# ARDUINO_POWER_UNIT1.net
KiCad netlist of a schematic drawn in EAGLE
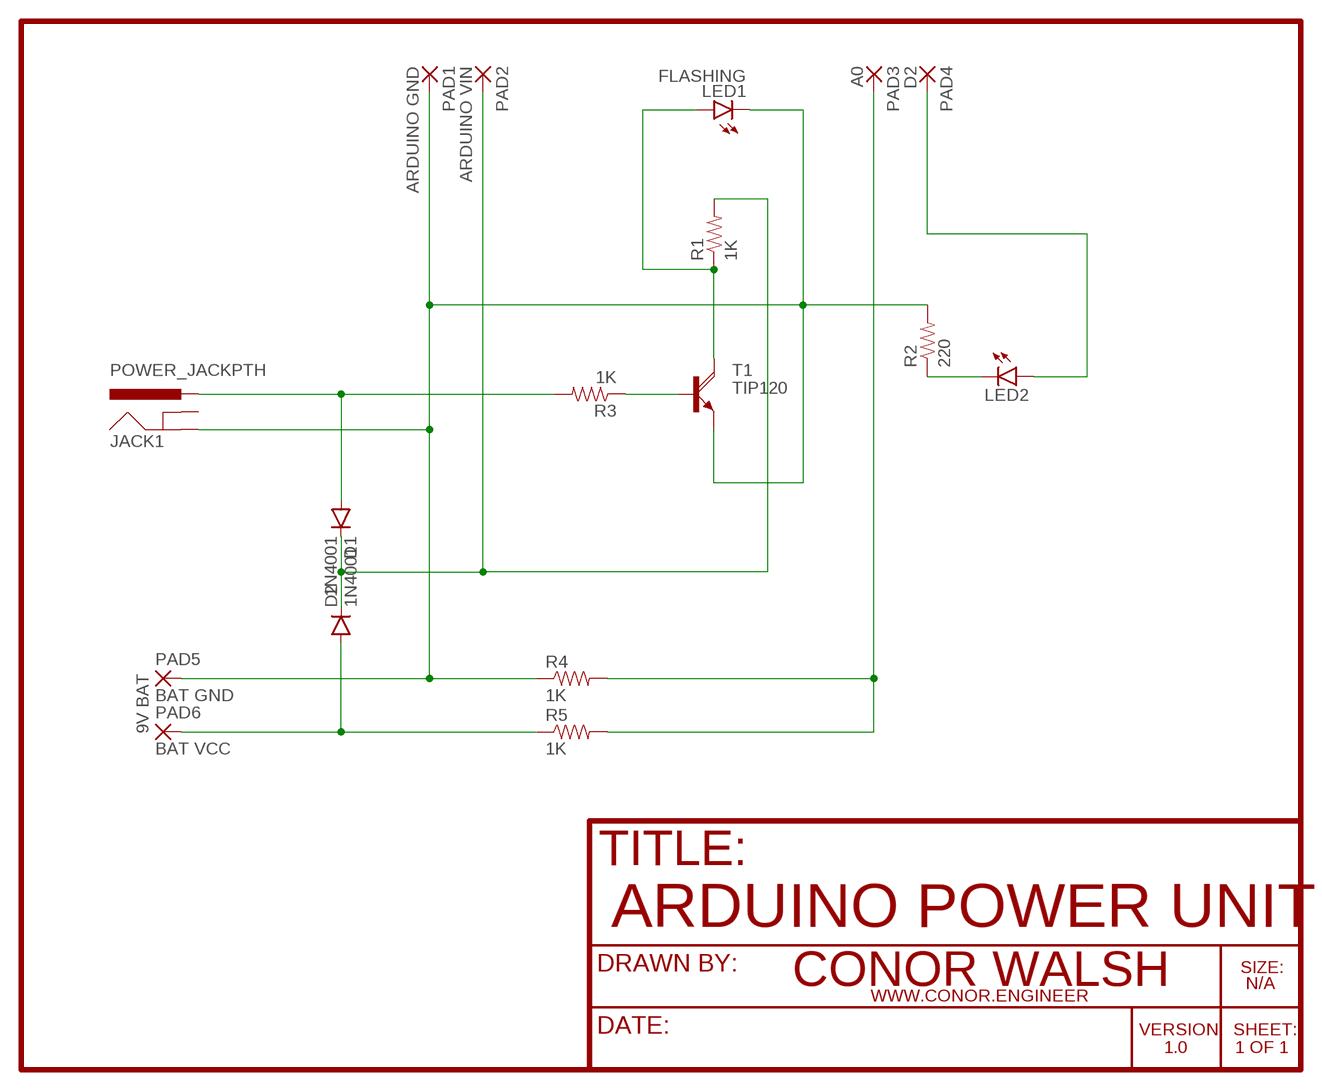
[diagram p0: schematic, sheet 1]

(export (version "E")
  (design (tool "Eeschema 10.0.6"))
  (components
    (comp (ref "D1")
      (value "1N4001")
      (footprint "eagle-import:DIODE-1N4148")
      (libsource (lib "eagle-import") (part "DIODE1N4148"))
    )
    (comp (ref "D2")
      (value "1N4001")
      (footprint "eagle-import:DIODE-1N4148")
      (libsource (lib "eagle-import") (part "DIODE1N4148"))
    )
    (comp (ref "JACK1")
      (value "POWER_JACKPTH")
      (footprint "eagle-import:POWER_JACK_PTH")
      (libsource (lib "eagle-import") (part "POWER_JACKPTH"))
    )
    (comp (ref "LED1")
      (value "FLASHING")
      (footprint "eagle-import:LED5MM")
      (libsource (lib "eagle-import") (part "LED5MM"))
    )
    (comp (ref "LED2")
      (value "LED5MM")
      (footprint "eagle-import:LED5MM")
      (libsource (lib "eagle-import") (part "LED5MM"))
    )
    (comp (ref "PAD1")
      (value "ARDUINO GND")
      (footprint "eagle-import:2,54_0,9")
      (libsource (lib "eagle-import") (part "2,54/0,9"))
    )
    (comp (ref "PAD2")
      (value "ARDUINO VIN")
      (footprint "eagle-import:2,54_0,9")
      (libsource (lib "eagle-import") (part "2,54/0,9"))
    )
    (comp (ref "PAD3")
      (value "A0")
      (footprint "eagle-import:2,54_0,9")
      (libsource (lib "eagle-import") (part "2,54/0,9"))
    )
    (comp (ref "PAD4")
      (value "D2")
      (footprint "eagle-import:2,54_0,9")
      (libsource (lib "eagle-import") (part "2,54/0,9"))
    )
    (comp (ref "PAD5")
      (value "BAT GND")
      (footprint "eagle-import:2,54_0,9")
      (libsource (lib "eagle-import") (part "2,54/0,9"))
    )
    (comp (ref "PAD6")
      (value "BAT VCC")
      (footprint "eagle-import:2,54_0,9")
      (libsource (lib "eagle-import") (part "2,54/0,9"))
    )
    (comp (ref "R1")
      (value "1K")
      (footprint "eagle-import:AXIAL-0.4")
      (libsource (lib "eagle-import") (part "RESISTORPTH-1/4W"))
    )
    (comp (ref "R2")
      (value "220")
      (footprint "eagle-import:AXIAL-0.4")
      (libsource (lib "eagle-import") (part "RESISTORPTH-1/4W"))
    )
    (comp (ref "R3")
      (value "1K")
      (footprint "eagle-import:AXIAL-0.4")
      (libsource (lib "eagle-import") (part "RESISTORPTH-1/4W"))
    )
    (comp (ref "R4")
      (value "1K")
      (footprint "eagle-import:AXIAL-0.4")
      (libsource (lib "eagle-import") (part "RESISTORPTH-1/4W"))
    )
    (comp (ref "R5")
      (value "1K")
      (footprint "eagle-import:AXIAL-0.4")
      (libsource (lib "eagle-import") (part "RESISTORPTH-1/4W"))
    )
    (comp (ref "T1")
      (value "TIP120")
      (footprint "eagle-import:TO220AH")
      (libsource (lib "eagle-import") (part "TIP120"))
    )
  )
  (nets
    (net (code "1") (name "Net-(LED1-C)") (class "Default")
      (node (ref "JACK1") (pin "GND") (pinfunction "GND_GND") (pintype "bidirectional"))
      (node (ref "LED1") (pin "K") (pinfunction "C_K") (pintype "passive"))
      (node (ref "PAD1") (pin "1") (pinfunction "P_1") (pintype "passive"))
      (node (ref "PAD5") (pin "1") (pinfunction "P_1") (pintype "passive"))
      (node (ref "R2") (pin "P$2") (pinfunction "2_P$2") (pintype "passive"))
      (node (ref "R4") (pin "P$1") (pinfunction "1_P$1") (pintype "passive"))
      (node (ref "T1") (pin "E") (pinfunction "E_E") (pintype "passive"))
    )
    (net (code "2") (name "Net-(LED2-C)") (class "Default")
      (node (ref "LED2") (pin "K") (pinfunction "C_K") (pintype "passive"))
      (node (ref "R2") (pin "P$1") (pinfunction "1_P$1") (pintype "passive"))
    )
    (net (code "3") (name "Net-(PAD2-P)") (class "Default")
      (node (ref "D1") (pin "C") (pinfunction "C_C") (pintype "passive"))
      (node (ref "D2") (pin "C") (pinfunction "C_C") (pintype "passive"))
      (node (ref "PAD2") (pin "1") (pinfunction "P_1") (pintype "passive"))
      (node (ref "R1") (pin "P$2") (pinfunction "2_P$2") (pintype "passive"))
    )
    (net (code "4") (name "Net-(PAD3-P)") (class "Default")
      (node (ref "PAD3") (pin "1") (pinfunction "P_1") (pintype "passive"))
      (node (ref "R4") (pin "P$2") (pinfunction "2_P$2") (pintype "passive"))
      (node (ref "R5") (pin "P$2") (pinfunction "2_P$2") (pintype "passive"))
    )
    (net (code "5") (name "Net-(PAD4-P)") (class "Default")
      (node (ref "LED2") (pin "A") (pinfunction "A_A") (pintype "passive"))
      (node (ref "PAD4") (pin "1") (pinfunction "P_1") (pintype "passive"))
    )
    (net (code "6") (name "Net-(PAD6-P)") (class "Default")
      (node (ref "D2") (pin "A") (pinfunction "A_A") (pintype "passive"))
      (node (ref "PAD6") (pin "1") (pinfunction "P_1") (pintype "passive"))
      (node (ref "R5") (pin "P$1") (pinfunction "1_P$1") (pintype "passive"))
    )
    (net (code "7") (name "Net-(R1-1)") (class "Default")
      (node (ref "LED1") (pin "A") (pinfunction "A_A") (pintype "passive"))
      (node (ref "R1") (pin "P$1") (pinfunction "1_P$1") (pintype "passive"))
      (node (ref "T1") (pin "C") (pinfunction "C_C") (pintype "passive"))
    )
    (net (code "8") (name "Net-(R3-1)") (class "Default")
      (node (ref "R3") (pin "P$1") (pinfunction "1_P$1") (pintype "passive"))
      (node (ref "T1") (pin "B") (pinfunction "B_B") (pintype "passive"))
    )
    (net (code "9") (name "Net-(R3-2)") (class "Default")
      (node (ref "D1") (pin "A") (pinfunction "A_A") (pintype "passive"))
      (node (ref "JACK1") (pin "PWR") (pinfunction "PWR_PWR") (pintype "bidirectional"))
      (node (ref "R3") (pin "P$2") (pinfunction "2_P$2") (pintype "passive"))
    )
    (net (code "10") (name "unconnected-(JACK1-PadGNDBREAK)") (class "Default")
      (node (ref "JACK1") (pin "GNDBREAK") (pinfunction "GNDBREAK_GNDBREAK") (pintype "bidirectional"))
    )
  )
)
